# MemoryStorage.net
KiCad netlist of a schematic drawn in Altium Designer
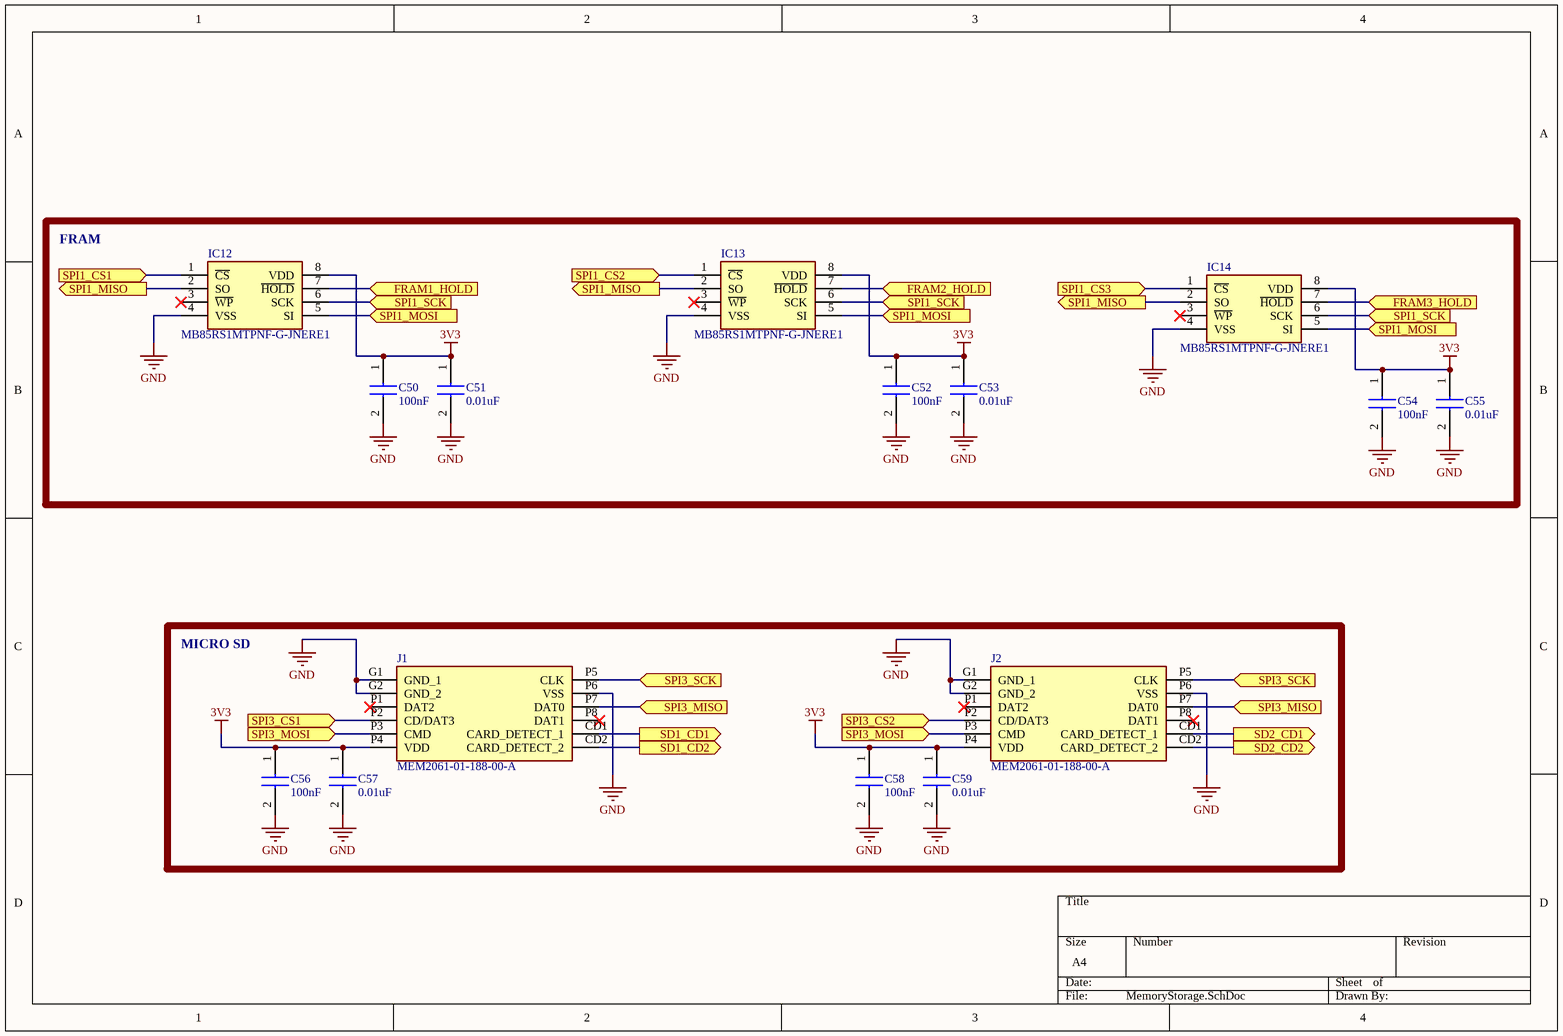
[diagram p0: MemoryStorage.SchDoc]

(export (version "E")
  (design (tool "Eeschema 10.0.6"))
  (components
    (comp (ref "C50")
      (value "100nF")
      (footprint "RT_IS:CAPC1608X95N")
      (description "0.1 µF ±20% 16V Ceramic Capacitor X7R 0603 (1608 Metric)")
      (fields (field (name "MANUFACTURER_PART_NUMBER") "C0603C104M4RAC7867"))
      (libsource (lib "*") (part "C0603C104M4RAC7867"))
    )
    (comp (ref "C51")
      (value "0.01uF")
      (footprint "RT_IS:C0603")
      (description "10000 pF ±10% 63V Ceramic Capacitor X7R 0603 (1608 Metric)")
      (fields
        (field (name "MANUFACTURER_PART_NUMBER") "C0603C103KMRECAUTO")
        (field (name "MOUSER PART NUMBER") "80-C0603C103KMREAUTO")
      )
      (libsource (lib "*") (part "C0603C103KMRECAUTO"))
    )
    (comp (ref "C52")
      (value "100nF")
      (footprint "RT_IS:CAPC1608X95N")
      (description "0.1 µF ±20% 16V Ceramic Capacitor X7R 0603 (1608 Metric)")
      (fields (field (name "MANUFACTURER_PART_NUMBER") "C0603C104M4RAC7867"))
      (libsource (lib "*") (part "C0603C104M4RAC7867"))
    )
    (comp (ref "C53")
      (value "0.01uF")
      (footprint "RT_IS:C0603")
      (description "10000 pF ±10% 63V Ceramic Capacitor X7R 0603 (1608 Metric)")
      (fields
        (field (name "MANUFACTURER_PART_NUMBER") "C0603C103KMRECAUTO")
        (field (name "MOUSER PART NUMBER") "80-C0603C103KMREAUTO")
      )
      (libsource (lib "*") (part "C0603C103KMRECAUTO"))
    )
    (comp (ref "C54")
      (value "100nF")
      (footprint "RT_IS:CAPC1608X95N")
      (description "0.1 µF ±20% 16V Ceramic Capacitor X7R 0603 (1608 Metric)")
      (fields (field (name "MANUFACTURER_PART_NUMBER") "C0603C104M4RAC7867"))
      (libsource (lib "*") (part "C0603C104M4RAC7867"))
    )
    (comp (ref "C55")
      (value "0.01uF")
      (footprint "RT_IS:C0603")
      (description "10000 pF ±10% 63V Ceramic Capacitor X7R 0603 (1608 Metric)")
      (fields
        (field (name "MANUFACTURER_PART_NUMBER") "C0603C103KMRECAUTO")
        (field (name "MOUSER PART NUMBER") "80-C0603C103KMREAUTO")
      )
      (libsource (lib "*") (part "C0603C103KMRECAUTO"))
    )
    (comp (ref "C56")
      (value "100nF")
      (footprint "RT_IS:CAPC1608X95N")
      (description "0.1 µF ±20% 16V Ceramic Capacitor X7R 0603 (1608 Metric)")
      (fields (field (name "MANUFACTURER_PART_NUMBER") "C0603C104M4RAC7867"))
      (libsource (lib "*") (part "C0603C104M4RAC7867"))
    )
    (comp (ref "C57")
      (value "0.01uF")
      (footprint "RT_IS:C0603")
      (description "10000 pF ±10% 63V Ceramic Capacitor X7R 0603 (1608 Metric)")
      (fields
        (field (name "MANUFACTURER_PART_NUMBER") "C0603C103KMRECAUTO")
        (field (name "MOUSER PART NUMBER") "80-C0603C103KMREAUTO")
      )
      (libsource (lib "*") (part "C0603C103KMRECAUTO"))
    )
    (comp (ref "C58")
      (value "100nF")
      (footprint "RT_IS:CAPC1608X95N")
      (description "0.1 µF ±20% 16V Ceramic Capacitor X7R 0603 (1608 Metric)")
      (fields (field (name "MANUFACTURER_PART_NUMBER") "C0603C104M4RAC7867"))
      (libsource (lib "*") (part "C0603C104M4RAC7867"))
    )
    (comp (ref "C59")
      (value "0.01uF")
      (footprint "RT_IS:C0603")
      (description "10000 pF ±10% 63V Ceramic Capacitor X7R 0603 (1608 Metric)")
      (fields
        (field (name "MANUFACTURER_PART_NUMBER") "C0603C103KMRECAUTO")
        (field (name "MOUSER PART NUMBER") "80-C0603C103KMREAUTO")
      )
      (libsource (lib "*") (part "C0603C103KMRECAUTO"))
    )
    (comp (ref "IC12")
      (value "MB85RS1MTPNF-G-JNERE1")
      (footprint "RT_IS:SOIC127P600X175-8N")
      (description "FRAM (Ferroelectric RAM) Memory IC 1Mbit SPI 40 MHz 8-SOP")
      (fields (field (name "MOUSER PART NUMBER") "249-85S1MTPNFGJNERE1"))
      (libsource (lib "*") (part "MB85RS1MTPNF-G-JNERE1"))
    )
    (comp (ref "IC13")
      (value "MB85RS1MTPNF-G-JNERE1")
      (footprint "RT_IS:SOIC127P600X175-8N")
      (description "FRAM (Ferroelectric RAM) Memory IC 1Mbit SPI 40 MHz 8-SOP")
      (fields (field (name "MOUSER PART NUMBER") "249-85S1MTPNFGJNERE1"))
      (libsource (lib "*") (part "MB85RS1MTPNF-G-JNERE1"))
    )
    (comp (ref "IC14")
      (value "MB85RS1MTPNF-G-JNERE1")
      (footprint "RT_IS:SOIC127P600X175-8N")
      (description "FRAM (Ferroelectric RAM) Memory IC 1Mbit SPI 40 MHz 8-SOP")
      (fields (field (name "MOUSER PART NUMBER") "249-85S1MTPNFGJNERE1"))
      (libsource (lib "*") (part "MB85RS1MTPNF-G-JNERE1"))
    )
    (comp (ref "J1")
      (value "MEM2061-01-188-00-A")
      (footprint "RT_IS:MEM20610118800A")
      (description "MICRO SD PUSH PUSH, CLOSED, SMT,")
      (libsource (lib "*") (part "MEM2061-01-188-00-A"))
    )
    (comp (ref "J2")
      (value "MEM2061-01-188-00-A")
      (footprint "RT_IS:MEM20610118800A")
      (description "MICRO SD PUSH PUSH, CLOSED, SMT,")
      (libsource (lib "*") (part "MEM2061-01-188-00-A"))
    )
  )
  (nets
    (net (code "1") (name "/FRAM1_HOLD") (class "Default")
      (node (ref "IC12") (pin "7") (pinfunction "~{HOLD}_7") (pintype "passive"))
    )
    (net (code "2") (name "/FRAM2_HOLD") (class "Default")
      (node (ref "IC13") (pin "7") (pinfunction "~{HOLD}_7") (pintype "passive"))
    )
    (net (code "3") (name "/FRAM3_HOLD") (class "Default")
      (node (ref "IC14") (pin "7") (pinfunction "~{HOLD}_7") (pintype "passive"))
    )
    (net (code "4") (name "/SD1_CD1") (class "Default")
      (node (ref "J1") (pin "CD1") (pinfunction "CARD_DETECT_1_CD1") (pintype "passive"))
    )
    (net (code "5") (name "/SD1_CD2") (class "Default")
      (node (ref "J1") (pin "CD2") (pinfunction "CARD_DETECT_2_CD2") (pintype "passive"))
    )
    (net (code "6") (name "/SD2_CD1") (class "Default")
      (node (ref "J2") (pin "CD1") (pinfunction "CARD_DETECT_1_CD1") (pintype "passive"))
    )
    (net (code "7") (name "/SD2_CD2") (class "Default")
      (node (ref "J2") (pin "CD2") (pinfunction "CARD_DETECT_2_CD2") (pintype "passive"))
    )
    (net (code "8") (name "/SPI1_CS1") (class "Default")
      (node (ref "IC12") (pin "1") (pinfunction "~{CS}_1") (pintype "passive"))
    )
    (net (code "9") (name "/SPI1_CS2") (class "Default")
      (node (ref "IC13") (pin "1") (pinfunction "~{CS}_1") (pintype "passive"))
    )
    (net (code "10") (name "/SPI1_CS3") (class "Default")
      (node (ref "IC14") (pin "1") (pinfunction "~{CS}_1") (pintype "passive"))
    )
    (net (code "11") (name "/SPI1_MISO") (class "Default")
      (node (ref "IC12") (pin "2") (pinfunction "SO_2") (pintype "passive"))
      (node (ref "IC13") (pin "2") (pinfunction "SO_2") (pintype "passive"))
      (node (ref "IC14") (pin "2") (pinfunction "SO_2") (pintype "passive"))
    )
    (net (code "12") (name "/SPI1_MOSI") (class "Default")
      (node (ref "IC12") (pin "5") (pinfunction "SI_5") (pintype "passive"))
      (node (ref "IC13") (pin "5") (pinfunction "SI_5") (pintype "passive"))
      (node (ref "IC14") (pin "5") (pinfunction "SI_5") (pintype "passive"))
    )
    (net (code "13") (name "/SPI1_SCK") (class "Default")
      (node (ref "IC12") (pin "6") (pinfunction "SCK_6") (pintype "passive"))
      (node (ref "IC13") (pin "6") (pinfunction "SCK_6") (pintype "passive"))
      (node (ref "IC14") (pin "6") (pinfunction "SCK_6") (pintype "passive"))
    )
    (net (code "14") (name "/SPI3_CS1") (class "Default")
      (node (ref "J1") (pin "P2") (pinfunction "CD/DAT3_P2") (pintype "passive"))
    )
    (net (code "15") (name "/SPI3_CS2") (class "Default")
      (node (ref "J2") (pin "P2") (pinfunction "CD/DAT3_P2") (pintype "passive"))
    )
    (net (code "16") (name "/SPI3_MISO") (class "Default")
      (node (ref "J1") (pin "P7") (pinfunction "DAT0_P7") (pintype "passive"))
      (node (ref "J2") (pin "P7") (pinfunction "DAT0_P7") (pintype "passive"))
    )
    (net (code "17") (name "/SPI3_MOSI") (class "Default")
      (node (ref "J1") (pin "P3") (pinfunction "CMD_P3") (pintype "passive"))
      (node (ref "J2") (pin "P3") (pinfunction "CMD_P3") (pintype "passive"))
    )
    (net (code "18") (name "/SPI3_SCK") (class "Default")
      (node (ref "J1") (pin "P5") (pinfunction "CLK_P5") (pintype "passive"))
      (node (ref "J2") (pin "P5") (pinfunction "CLK_P5") (pintype "passive"))
    )
    (net (code "19") (name "3V3") (class "Default")
      (node (ref "C50") (pin "1") (pinfunction "1_1") (pintype "passive"))
      (node (ref "C51") (pin "1") (pinfunction "1_1") (pintype "passive"))
      (node (ref "C52") (pin "1") (pinfunction "1_1") (pintype "passive"))
      (node (ref "C53") (pin "1") (pinfunction "1_1") (pintype "passive"))
      (node (ref "C54") (pin "1") (pinfunction "1_1") (pintype "passive"))
      (node (ref "C55") (pin "1") (pinfunction "1_1") (pintype "passive"))
      (node (ref "C56") (pin "1") (pinfunction "1_1") (pintype "passive"))
      (node (ref "C57") (pin "1") (pinfunction "1_1") (pintype "passive"))
      (node (ref "C58") (pin "1") (pinfunction "1_1") (pintype "passive"))
      (node (ref "C59") (pin "1") (pinfunction "1_1") (pintype "passive"))
      (node (ref "IC12") (pin "8") (pinfunction "VDD_8") (pintype "passive"))
      (node (ref "IC13") (pin "8") (pinfunction "VDD_8") (pintype "passive"))
      (node (ref "IC14") (pin "8") (pinfunction "VDD_8") (pintype "passive"))
      (node (ref "J1") (pin "P4") (pinfunction "VDD_P4") (pintype "passive"))
      (node (ref "J2") (pin "P4") (pinfunction "VDD_P4") (pintype "passive"))
    )
    (net (code "20") (name "GND") (class "Default")
      (node (ref "C50") (pin "2") (pinfunction "2_2") (pintype "passive"))
      (node (ref "C51") (pin "2") (pinfunction "2_2") (pintype "passive"))
      (node (ref "C52") (pin "2") (pinfunction "2_2") (pintype "passive"))
      (node (ref "C53") (pin "2") (pinfunction "2_2") (pintype "passive"))
      (node (ref "C54") (pin "2") (pinfunction "2_2") (pintype "passive"))
      (node (ref "C55") (pin "2") (pinfunction "2_2") (pintype "passive"))
      (node (ref "C56") (pin "2") (pinfunction "2_2") (pintype "passive"))
      (node (ref "C57") (pin "2") (pinfunction "2_2") (pintype "passive"))
      (node (ref "C58") (pin "2") (pinfunction "2_2") (pintype "passive"))
      (node (ref "C59") (pin "2") (pinfunction "2_2") (pintype "passive"))
      (node (ref "IC12") (pin "4") (pinfunction "VSS_4") (pintype "passive"))
      (node (ref "IC13") (pin "4") (pinfunction "VSS_4") (pintype "passive"))
      (node (ref "IC14") (pin "4") (pinfunction "VSS_4") (pintype "passive"))
      (node (ref "J1") (pin "G1") (pinfunction "GND_1_G1") (pintype "passive"))
      (node (ref "J1") (pin "G2") (pinfunction "GND_2_G2") (pintype "passive"))
      (node (ref "J1") (pin "P6") (pinfunction "VSS_P6") (pintype "passive"))
      (node (ref "J2") (pin "G1") (pinfunction "GND_1_G1") (pintype "passive"))
      (node (ref "J2") (pin "G2") (pinfunction "GND_2_G2") (pintype "passive"))
      (node (ref "J2") (pin "P6") (pinfunction "VSS_P6") (pintype "passive"))
    )
    (net (code "21") (name "unconnected-(IC12-~{WP}-Pad3)") (class "Default")
      (node (ref "IC12") (pin "3") (pinfunction "~{WP}_3") (pintype "passive+no_connect"))
    )
    (net (code "22") (name "unconnected-(IC13-~{WP}-Pad3)") (class "Default")
      (node (ref "IC13") (pin "3") (pinfunction "~{WP}_3") (pintype "passive+no_connect"))
    )
    (net (code "23") (name "unconnected-(IC14-~{WP}-Pad3)") (class "Default")
      (node (ref "IC14") (pin "3") (pinfunction "~{WP}_3") (pintype "passive+no_connect"))
    )
    (net (code "24") (name "unconnected-(J1-DAT1-PadP8)") (class "Default")
      (node (ref "J1") (pin "P8") (pinfunction "DAT1_P8") (pintype "passive+no_connect"))
    )
    (net (code "25") (name "unconnected-(J1-DAT2-PadP1)") (class "Default")
      (node (ref "J1") (pin "P1") (pinfunction "DAT2_P1") (pintype "passive+no_connect"))
    )
    (net (code "26") (name "unconnected-(J2-DAT1-PadP8)") (class "Default")
      (node (ref "J2") (pin "P8") (pinfunction "DAT1_P8") (pintype "passive+no_connect"))
    )
    (net (code "27") (name "unconnected-(J2-DAT2-PadP1)") (class "Default")
      (node (ref "J2") (pin "P1") (pinfunction "DAT2_P1") (pintype "passive+no_connect"))
    )
  )
)
